# BJT.net
KiCad netlist of a schematic drawn in Altium Designer
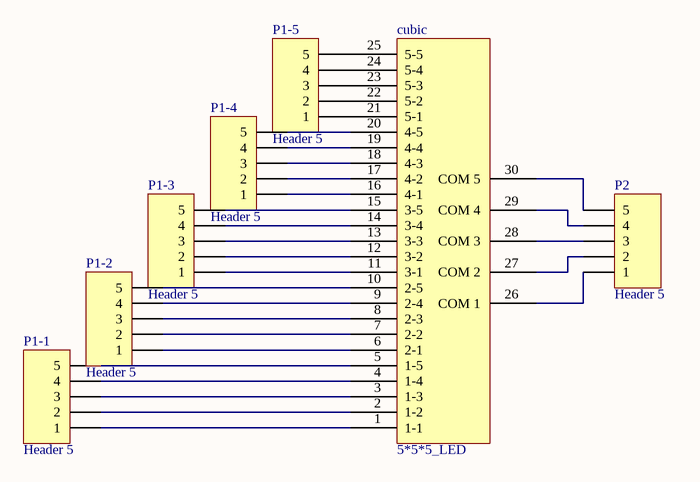
[diagram p0: BJT.SchDoc]

(export (version "E")
  (design (tool "Eeschema 10.0.6"))
  (components
    (comp (ref "cubic")
      (value "5*5*5_LED")
      (footprint "PCBComponent_1")
      (libsource (lib "Schlib1") (part "5*5*5_LED"))
    )
    (comp (ref "P1-1")
      (value "Header 5")
      (footprint "HDR1X5")
      (description "Header, 5-Pin")
      (fields (field (name "PUBLISHER") "Altium Limited"))
      (libsource (lib "Miscellaneous Connectors") (part "Header 5"))
    )
    (comp (ref "P1-2")
      (value "Header 5")
      (footprint "HDR1X5")
      (description "Header, 5-Pin")
      (fields (field (name "PUBLISHER") "Altium Limited"))
      (libsource (lib "Miscellaneous Connectors") (part "Header 5"))
    )
    (comp (ref "P1-3")
      (value "Header 5")
      (footprint "HDR1X5")
      (description "Header, 5-Pin")
      (fields (field (name "PUBLISHER") "Altium Limited"))
      (libsource (lib "Miscellaneous Connectors") (part "Header 5"))
    )
    (comp (ref "P1-4")
      (value "Header 5")
      (footprint "HDR1X5")
      (description "Header, 5-Pin")
      (fields (field (name "PUBLISHER") "Altium Limited"))
      (libsource (lib "Miscellaneous Connectors") (part "Header 5"))
    )
    (comp (ref "P1-5")
      (value "Header 5")
      (footprint "HDR1X5")
      (description "Header, 5-Pin")
      (fields (field (name "PUBLISHER") "Altium Limited"))
      (libsource (lib "Miscellaneous Connectors") (part "Header 5"))
    )
    (comp (ref "P2")
      (value "Header 5")
      (footprint "HDR1X5")
      (description "Header, 5-Pin")
      (fields (field (name "PUBLISHER") "Altium Limited"))
      (libsource (lib "") (part "Header 5_1"))
    )
  )
  (nets
    (net (code "1") (name "Net-(cubic-1-1)") (class "Default")
      (node (ref "P1-1") (pin "1") (pinfunction "1_1") (pintype "passive"))
      (node (ref "cubic") (pin "1") (pinfunction "1-1_1") (pintype "passive"))
    )
    (net (code "2") (name "Net-(cubic-1-2)") (class "Default")
      (node (ref "P1-1") (pin "2") (pinfunction "2_2") (pintype "passive"))
      (node (ref "cubic") (pin "2") (pinfunction "1-2_2") (pintype "passive"))
    )
    (net (code "3") (name "Net-(cubic-1-3)") (class "Default")
      (node (ref "P1-1") (pin "3") (pinfunction "3_3") (pintype "passive"))
      (node (ref "cubic") (pin "3") (pinfunction "1-3_3") (pintype "passive"))
    )
    (net (code "4") (name "Net-(cubic-1-4)") (class "Default")
      (node (ref "P1-1") (pin "4") (pinfunction "4_4") (pintype "passive"))
      (node (ref "cubic") (pin "4") (pinfunction "1-4_4") (pintype "passive"))
    )
    (net (code "5") (name "Net-(cubic-1-5)") (class "Default")
      (node (ref "P1-1") (pin "5") (pinfunction "5_5") (pintype "passive"))
      (node (ref "cubic") (pin "5") (pinfunction "1-5_5") (pintype "passive"))
    )
    (net (code "6") (name "Net-(cubic-2-1)") (class "Default")
      (node (ref "P1-2") (pin "1") (pinfunction "1_1") (pintype "passive"))
      (node (ref "cubic") (pin "6") (pinfunction "2-1_6") (pintype "passive"))
    )
    (net (code "7") (name "Net-(cubic-2-2)") (class "Default")
      (node (ref "P1-2") (pin "2") (pinfunction "2_2") (pintype "passive"))
      (node (ref "cubic") (pin "7") (pinfunction "2-2_7") (pintype "passive"))
    )
    (net (code "8") (name "Net-(cubic-2-3)") (class "Default")
      (node (ref "P1-2") (pin "3") (pinfunction "3_3") (pintype "passive"))
      (node (ref "cubic") (pin "8") (pinfunction "2-3_8") (pintype "passive"))
    )
    (net (code "9") (name "Net-(cubic-2-4)") (class "Default")
      (node (ref "P1-2") (pin "4") (pinfunction "4_4") (pintype "passive"))
      (node (ref "cubic") (pin "9") (pinfunction "2-4_9") (pintype "passive"))
    )
    (net (code "10") (name "Net-(cubic-2-5)") (class "Default")
      (node (ref "P1-2") (pin "5") (pinfunction "5_5") (pintype "passive"))
      (node (ref "cubic") (pin "10") (pinfunction "2-5_10") (pintype "passive"))
    )
    (net (code "11") (name "Net-(cubic-3-1)") (class "Default")
      (node (ref "P1-3") (pin "1") (pinfunction "1_1") (pintype "passive"))
      (node (ref "cubic") (pin "11") (pinfunction "3-1_11") (pintype "passive"))
    )
    (net (code "12") (name "Net-(cubic-3-2)") (class "Default")
      (node (ref "P1-3") (pin "2") (pinfunction "2_2") (pintype "passive"))
      (node (ref "cubic") (pin "12") (pinfunction "3-2_12") (pintype "passive"))
    )
    (net (code "13") (name "Net-(cubic-3-3)") (class "Default")
      (node (ref "P1-3") (pin "3") (pinfunction "3_3") (pintype "passive"))
      (node (ref "cubic") (pin "13") (pinfunction "3-3_13") (pintype "passive"))
    )
    (net (code "14") (name "Net-(cubic-3-4)") (class "Default")
      (node (ref "P1-3") (pin "4") (pinfunction "4_4") (pintype "passive"))
      (node (ref "cubic") (pin "14") (pinfunction "3-4_14") (pintype "passive"))
    )
    (net (code "15") (name "Net-(cubic-3-5)") (class "Default")
      (node (ref "P1-3") (pin "5") (pinfunction "5_5") (pintype "passive"))
      (node (ref "cubic") (pin "15") (pinfunction "3-5_15") (pintype "passive"))
    )
    (net (code "16") (name "Net-(cubic-4-1)") (class "Default")
      (node (ref "P1-4") (pin "1") (pinfunction "1_1") (pintype "passive"))
      (node (ref "cubic") (pin "16") (pinfunction "4-1_16") (pintype "passive"))
    )
    (net (code "17") (name "Net-(cubic-4-2)") (class "Default")
      (node (ref "P1-4") (pin "2") (pinfunction "2_2") (pintype "passive"))
      (node (ref "cubic") (pin "17") (pinfunction "4-2_17") (pintype "passive"))
    )
    (net (code "18") (name "Net-(cubic-4-3)") (class "Default")
      (node (ref "P1-4") (pin "3") (pinfunction "3_3") (pintype "passive"))
      (node (ref "cubic") (pin "18") (pinfunction "4-3_18") (pintype "passive"))
    )
    (net (code "19") (name "Net-(cubic-4-4)") (class "Default")
      (node (ref "P1-4") (pin "4") (pinfunction "4_4") (pintype "passive"))
      (node (ref "cubic") (pin "19") (pinfunction "4-4_19") (pintype "passive"))
    )
    (net (code "20") (name "Net-(cubic-4-5)") (class "Default")
      (node (ref "P1-4") (pin "5") (pinfunction "5_5") (pintype "passive"))
      (node (ref "cubic") (pin "20") (pinfunction "4-5_20") (pintype "passive"))
    )
    (net (code "21") (name "Net-(cubic-5-1)") (class "Default")
      (node (ref "P1-5") (pin "1") (pinfunction "1_1") (pintype "passive"))
      (node (ref "cubic") (pin "21") (pinfunction "5-1_21") (pintype "passive"))
    )
    (net (code "22") (name "Net-(cubic-5-2)") (class "Default")
      (node (ref "P1-5") (pin "2") (pinfunction "2_2") (pintype "passive"))
      (node (ref "cubic") (pin "22") (pinfunction "5-2_22") (pintype "passive"))
    )
    (net (code "23") (name "Net-(cubic-5-3)") (class "Default")
      (node (ref "P1-5") (pin "3") (pinfunction "3_3") (pintype "passive"))
      (node (ref "cubic") (pin "23") (pinfunction "5-3_23") (pintype "passive"))
    )
    (net (code "24") (name "Net-(cubic-5-4)") (class "Default")
      (node (ref "P1-5") (pin "4") (pinfunction "4_4") (pintype "passive"))
      (node (ref "cubic") (pin "24") (pinfunction "5-4_24") (pintype "passive"))
    )
    (net (code "25") (name "Net-(cubic-5-5)") (class "Default")
      (node (ref "P1-5") (pin "5") (pinfunction "5_5") (pintype "passive"))
      (node (ref "cubic") (pin "25") (pinfunction "5-5_25") (pintype "passive"))
    )
    (net (code "26") (name "Net-(cubic-COM_1)") (class "Default")
      (node (ref "P2") (pin "1") (pinfunction "1_1") (pintype "passive"))
      (node (ref "cubic") (pin "26") (pinfunction "COM_1_26") (pintype "passive"))
    )
    (net (code "27") (name "Net-(cubic-COM_2)") (class "Default")
      (node (ref "P2") (pin "2") (pinfunction "2_2") (pintype "passive"))
      (node (ref "cubic") (pin "27") (pinfunction "COM_2_27") (pintype "passive"))
    )
    (net (code "28") (name "Net-(cubic-COM_3)") (class "Default")
      (node (ref "P2") (pin "3") (pinfunction "3_3") (pintype "passive"))
      (node (ref "cubic") (pin "28") (pinfunction "COM_3_28") (pintype "passive"))
    )
    (net (code "29") (name "Net-(cubic-COM_4)") (class "Default")
      (node (ref "P2") (pin "4") (pinfunction "4_4") (pintype "passive"))
      (node (ref "cubic") (pin "29") (pinfunction "COM_4_29") (pintype "passive"))
    )
    (net (code "30") (name "Net-(cubic-COM_5)") (class "Default")
      (node (ref "P2") (pin "5") (pinfunction "5_5") (pintype "passive"))
      (node (ref "cubic") (pin "30") (pinfunction "COM_5_30") (pintype "passive"))
    )
  )
)
